# UD3_1_N_P_Gate_Driver.net
KiCad netlist of a schematic drawn in Altium Designer
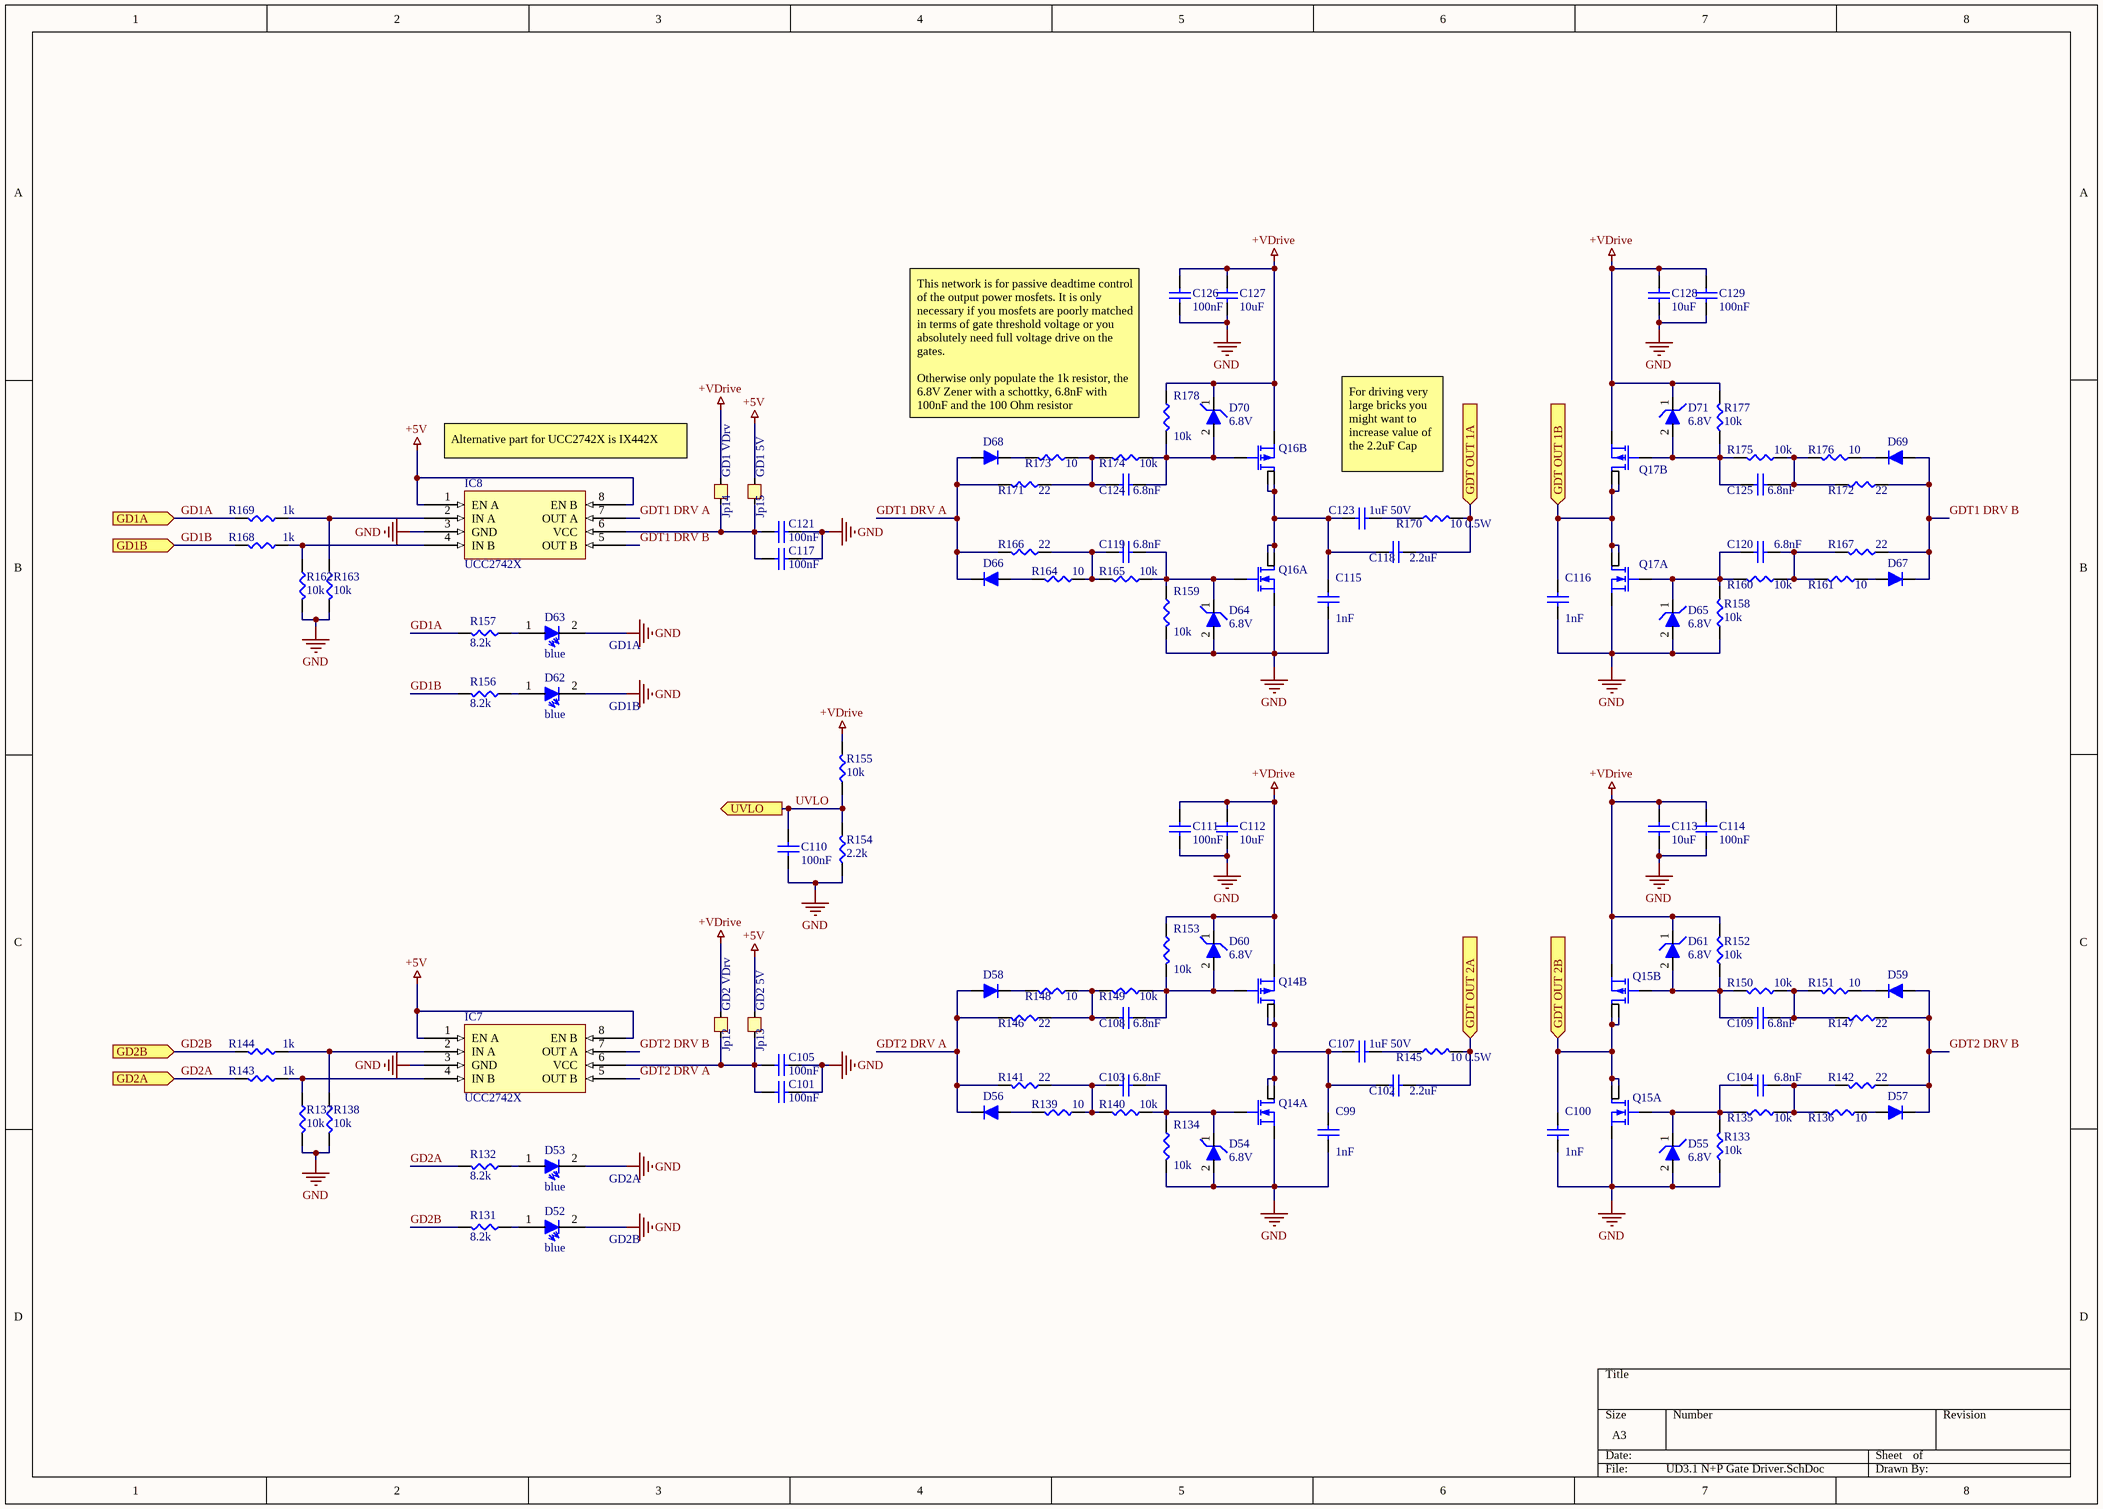
[diagram p0: UD3.1 N+P Gate Driver.SchDoc]

(export (version "E")
  (design (tool "Eeschema 10.0.6"))
  (components
    (comp (ref "C99") (value "1nF") (footprint "0603") (libsource (lib "stdLib") (part "Cap")))
    (comp (ref "C100") (value "1nF") (footprint "0603") (libsource (lib "stdLib") (part "Cap")))
    (comp (ref "C101") (value "100nF") (footprint "0603") (libsource (lib "stdLib") (part "Cap")))
    (comp (ref "C102") (value "2.2uF") (footprint "1210") (libsource (lib "stdLib") (part "Cap")))
    (comp (ref "C103") (value "6.8nF") (footprint "0603") (libsource (lib "stdLib") (part "Cap")))
    (comp (ref "C104") (value "6.8nF") (footprint "0603") (libsource (lib "stdLib") (part "Cap")))
    (comp (ref "C105") (value "100nF") (footprint "0603") (libsource (lib "stdLib") (part "Cap")))
    (comp (ref "C107") (value "1uF 50V") (footprint "1210") (libsource (lib "stdLib") (part "Cap")))
    (comp (ref "C108") (value "6.8nF") (footprint "0603") (libsource (lib "stdLib") (part "Cap")))
    (comp (ref "C109") (value "6.8nF") (footprint "0603") (libsource (lib "stdLib") (part "Cap")))
    (comp (ref "C110") (value "100nF") (footprint "0603") (libsource (lib "stdLib") (part "Cap")))
    (comp (ref "C111") (value "100nF") (footprint "0603") (libsource (lib "stdLib") (part "Cap")))
    (comp (ref "C112") (value "10uF") (footprint "0805") (libsource (lib "stdLib") (part "Cap")))
    (comp (ref "C113") (value "10uF") (footprint "0805") (libsource (lib "stdLib") (part "Cap")))
    (comp (ref "C114") (value "100nF") (footprint "0603") (libsource (lib "stdLib") (part "Cap")))
    (comp (ref "C115") (value "1nF") (footprint "0603") (libsource (lib "stdLib") (part "Cap")))
    (comp (ref "C116") (value "1nF") (footprint "0603") (libsource (lib "stdLib") (part "Cap")))
    (comp (ref "C117") (value "100nF") (footprint "0603") (libsource (lib "stdLib") (part "Cap")))
    (comp (ref "C118") (value "2.2uF") (footprint "1210") (libsource (lib "stdLib") (part "Cap")))
    (comp (ref "C119") (value "6.8nF") (footprint "0603") (libsource (lib "stdLib") (part "Cap")))
    (comp (ref "C120") (value "6.8nF") (footprint "0603") (libsource (lib "stdLib") (part "Cap")))
    (comp (ref "C121") (value "100nF") (footprint "0603") (libsource (lib "stdLib") (part "Cap")))
    (comp (ref "C123") (value "1uF 50V") (footprint "1210") (libsource (lib "stdLib") (part "Cap")))
    (comp (ref "C124") (value "6.8nF") (footprint "0603") (libsource (lib "stdLib") (part "Cap")))
    (comp (ref "C125") (value "6.8nF") (footprint "0603") (libsource (lib "stdLib") (part "Cap")))
    (comp (ref "C126") (value "100nF") (footprint "0603") (libsource (lib "stdLib") (part "Cap")))
    (comp (ref "C127") (value "10uF") (footprint "0805") (libsource (lib "stdLib") (part "Cap")))
    (comp (ref "C128") (value "10uF") (footprint "0805") (libsource (lib "stdLib") (part "Cap")))
    (comp (ref "C129") (value "100nF") (footprint "0603") (libsource (lib "stdLib") (part "Cap")))
    (comp (ref "D52")
      (value "blue")
      (footprint "1206 Reverse Mount")
      (description "Diode, but it lights up")
      (libsource (lib "stdLib") (part "LED"))
    )
    (comp (ref "D53")
      (value "blue")
      (footprint "1206 Reverse Mount")
      (description "Diode, but it lights up")
      (libsource (lib "stdLib") (part "LED"))
    )
    (comp (ref "D54") (value "6.8V") (footprint "SOD523") (libsource (lib "stdLib") (part "Diode Zener")))
    (comp (ref "D55") (value "6.8V") (footprint "SOD523") (libsource (lib "stdLib") (part "Diode Zener")))
    (comp (ref "D56")
      (value "Schottky 30V 100mA")
      (footprint "SOD523")
      (description "Cmon its a diode what more do I need to say?")
      (libsource (lib "stdLib") (part "Diode"))
    )
    (comp (ref "D57")
      (value "Schottky 30V 100mA")
      (footprint "SOD523")
      (description "Cmon its a diode what more do I need to say?")
      (libsource (lib "stdLib") (part "Diode"))
    )
    (comp (ref "D58")
      (value "Schottky 30V 100mA")
      (footprint "SOD523")
      (description "Cmon its a diode what more do I need to say?")
      (libsource (lib "stdLib") (part "Diode"))
    )
    (comp (ref "D59")
      (value "Schottky 30V 100mA")
      (footprint "SOD523")
      (description "Cmon its a diode what more do I need to say?")
      (libsource (lib "stdLib") (part "Diode"))
    )
    (comp (ref "D60") (value "6.8V") (footprint "SOD523") (libsource (lib "stdLib") (part "Diode Zener")))
    (comp (ref "D61") (value "6.8V") (footprint "SOD523") (libsource (lib "stdLib") (part "Diode Zener")))
    (comp (ref "D62")
      (value "blue")
      (footprint "1206 Reverse Mount")
      (description "Diode, but it lights up")
      (libsource (lib "stdLib") (part "LED"))
    )
    (comp (ref "D63")
      (value "blue")
      (footprint "1206 Reverse Mount")
      (description "Diode, but it lights up")
      (libsource (lib "stdLib") (part "LED"))
    )
    (comp (ref "D64") (value "6.8V") (footprint "SOD523") (libsource (lib "stdLib") (part "Diode Zener")))
    (comp (ref "D65") (value "6.8V") (footprint "SOD523") (libsource (lib "stdLib") (part "Diode Zener")))
    (comp (ref "D66")
      (value "Schottky 30V 100mA")
      (footprint "SOD523")
      (description "Cmon its a diode what more do I need to say?")
      (libsource (lib "stdLib") (part "Diode"))
    )
    (comp (ref "D67")
      (value "Schottky 30V 100mA")
      (footprint "SOD523")
      (description "Cmon its a diode what more do I need to say?")
      (libsource (lib "stdLib") (part "Diode"))
    )
    (comp (ref "D68")
      (value "Schottky 30V 100mA")
      (footprint "SOD523")
      (description "Cmon its a diode what more do I need to say?")
      (libsource (lib "stdLib") (part "Diode"))
    )
    (comp (ref "D69")
      (value "Schottky 30V 100mA")
      (footprint "SOD523")
      (description "Cmon its a diode what more do I need to say?")
      (libsource (lib "stdLib") (part "Diode"))
    )
    (comp (ref "D70") (value "6.8V") (footprint "SOD523") (libsource (lib "stdLib") (part "Diode Zener")))
    (comp (ref "D71") (value "6.8V") (footprint "SOD523") (libsource (lib "stdLib") (part "Diode Zener")))
    (comp (ref "IC7")
      (value "UCC2742X")
      (footprint "SOIC8")
      (description "Dual gate driver")
      (libsource (lib "stdLib") (part "UCC2742X"))
    )
    (comp (ref "IC8")
      (value "UCC2742X")
      (footprint "SOIC8")
      (description "Dual gate driver")
      (libsource (lib "stdLib") (part "UCC2742X"))
    )
    (comp (ref "Jp12")
      (value "GD2 VDrv")
      (footprint "PCB Jumper NO")
      (libsource (lib "stdLib") (part "Jumper"))
    )
    (comp (ref "Jp13")
      (value "GD2 5V")
      (footprint "PCB Jumper NO")
      (libsource (lib "stdLib") (part "Jumper"))
    )
    (comp (ref "Jp14")
      (value "GD1 VDrv")
      (footprint "PCB Jumper NO")
      (libsource (lib "stdLib") (part "Jumper"))
    )
    (comp (ref "Jp15")
      (value "GD1 5V")
      (footprint "PCB Jumper NO")
      (libsource (lib "stdLib") (part "Jumper"))
    )
    (comp (ref "Q14")
      (value "Mosfet 1N1P")
      (footprint "SO-8FL - Dual")
      (description "Dual Mosfet, one N & P channel resp.")
      (libsource (lib "stdLib") (part "Mosfet 1N1P"))
    )
    (comp (ref "Q15")
      (value "Mosfet 1N1P")
      (footprint "SO-8FL - Dual")
      (description "Dual Mosfet, one N & P channel resp.")
      (libsource (lib "stdLib") (part "Mosfet 1N1P"))
    )
    (comp (ref "Q16")
      (value "Mosfet 1N1P")
      (footprint "SO-8FL - Dual")
      (description "Dual Mosfet, one N & P channel resp.")
      (libsource (lib "stdLib") (part "Mosfet 1N1P"))
    )
    (comp (ref "Q17")
      (value "Mosfet 1N1P")
      (footprint "SO-8FL - Dual")
      (description "Dual Mosfet, one N & P channel resp.")
      (libsource (lib "stdLib") (part "Mosfet 1N1P"))
    )
    (comp (ref "R131") (value "8.2k") (footprint "0603") (libsource (lib "stdLib") (part "Resistor")))
    (comp (ref "R132") (value "8.2k") (footprint "0603") (libsource (lib "stdLib") (part "Resistor")))
    (comp (ref "R133") (value "10k") (footprint "0603") (libsource (lib "stdLib") (part "Resistor")))
    (comp (ref "R134") (value "10k") (footprint "0603") (libsource (lib "stdLib") (part "Resistor")))
    (comp (ref "R135") (value "10k") (footprint "0603") (libsource (lib "stdLib") (part "Resistor")))
    (comp (ref "R136") (value "10") (footprint "0603") (libsource (lib "stdLib") (part "Resistor")))
    (comp (ref "R137") (value "10k") (footprint "0603") (libsource (lib "stdLib") (part "Resistor")))
    (comp (ref "R138") (value "10k") (footprint "0603") (libsource (lib "stdLib") (part "Resistor")))
    (comp (ref "R139") (value "10") (footprint "0603") (libsource (lib "stdLib") (part "Resistor")))
    (comp (ref "R140") (value "10k") (footprint "0603") (libsource (lib "stdLib") (part "Resistor")))
    (comp (ref "R141") (value "22") (footprint "0603") (libsource (lib "stdLib") (part "Resistor")))
    (comp (ref "R142") (value "22") (footprint "0603") (libsource (lib "stdLib") (part "Resistor")))
    (comp (ref "R143") (value "1k") (footprint "0603") (libsource (lib "stdLib") (part "Resistor")))
    (comp (ref "R144") (value "1k") (footprint "0603") (libsource (lib "stdLib") (part "Resistor")))
    (comp (ref "R145") (value "10 0.5W") (footprint "1210") (libsource (lib "stdLib") (part "Resistor")))
    (comp (ref "R146") (value "22") (footprint "0603") (libsource (lib "stdLib") (part "Resistor")))
    (comp (ref "R147") (value "22") (footprint "0603") (libsource (lib "stdLib") (part "Resistor")))
    (comp (ref "R148") (value "10") (footprint "0603") (libsource (lib "stdLib") (part "Resistor")))
    (comp (ref "R149") (value "10k") (footprint "0603") (libsource (lib "stdLib") (part "Resistor")))
    (comp (ref "R150") (value "10k") (footprint "0603") (libsource (lib "stdLib") (part "Resistor")))
    (comp (ref "R151") (value "10") (footprint "0603") (libsource (lib "stdLib") (part "Resistor")))
    (comp (ref "R152") (value "10k") (footprint "0603") (libsource (lib "stdLib") (part "Resistor")))
    (comp (ref "R153") (value "10k") (footprint "0603") (libsource (lib "stdLib") (part "Resistor")))
    (comp (ref "R154") (value "2.2k") (footprint "0603") (libsource (lib "stdLib") (part "Resistor")))
    (comp (ref "R155") (value "10k") (footprint "0603") (libsource (lib "stdLib") (part "Resistor")))
    (comp (ref "R156") (value "8.2k") (footprint "0603") (libsource (lib "stdLib") (part "Resistor")))
    (comp (ref "R157") (value "8.2k") (footprint "0603") (libsource (lib "stdLib") (part "Resistor")))
    (comp (ref "R158") (value "10k") (footprint "0603") (libsource (lib "stdLib") (part "Resistor")))
    (comp (ref "R159") (value "10k") (footprint "0603") (libsource (lib "stdLib") (part "Resistor")))
    (comp (ref "R160") (value "10k") (footprint "0603") (libsource (lib "stdLib") (part "Resistor")))
    (comp (ref "R161") (value "10") (footprint "0603") (libsource (lib "stdLib") (part "Resistor")))
    (comp (ref "R162") (value "10k") (footprint "0603") (libsource (lib "stdLib") (part "Resistor")))
    (comp (ref "R163") (value "10k") (footprint "0603") (libsource (lib "stdLib") (part "Resistor")))
    (comp (ref "R164") (value "10") (footprint "0603") (libsource (lib "stdLib") (part "Resistor")))
    (comp (ref "R165") (value "10k") (footprint "0603") (libsource (lib "stdLib") (part "Resistor")))
    (comp (ref "R166") (value "22") (footprint "0603") (libsource (lib "stdLib") (part "Resistor")))
    (comp (ref "R167") (value "22") (footprint "0603") (libsource (lib "stdLib") (part "Resistor")))
    (comp (ref "R168") (value "1k") (footprint "0603") (libsource (lib "stdLib") (part "Resistor")))
    (comp (ref "R169") (value "1k") (footprint "0603") (libsource (lib "stdLib") (part "Resistor")))
    (comp (ref "R170") (value "10 0.5W") (footprint "1210") (libsource (lib "stdLib") (part "Resistor")))
    (comp (ref "R171") (value "22") (footprint "0603") (libsource (lib "stdLib") (part "Resistor")))
    (comp (ref "R172") (value "22") (footprint "0603") (libsource (lib "stdLib") (part "Resistor")))
    (comp (ref "R173") (value "10") (footprint "0603") (libsource (lib "stdLib") (part "Resistor")))
    (comp (ref "R174") (value "10k") (footprint "0603") (libsource (lib "stdLib") (part "Resistor")))
    (comp (ref "R175") (value "10k") (footprint "0603") (libsource (lib "stdLib") (part "Resistor")))
    (comp (ref "R176") (value "10") (footprint "0603") (libsource (lib "stdLib") (part "Resistor")))
    (comp (ref "R177") (value "10k") (footprint "0603") (libsource (lib "stdLib") (part "Resistor")))
    (comp (ref "R178") (value "10k") (footprint "0603") (libsource (lib "stdLib") (part "Resistor")))
  )
  (nets
    (net (code "1") (name "+5V") (class "Default")
      (node (ref "IC7") (pin "1") (pinfunction "EN_A_1") (pintype "input"))
      (node (ref "IC7") (pin "8") (pinfunction "EN_B_8") (pintype "input"))
      (node (ref "IC8") (pin "1") (pinfunction "EN_A_1") (pintype "input"))
      (node (ref "IC8") (pin "8") (pinfunction "EN_B_8") (pintype "input"))
      (node (ref "Jp13") (pin "2") (pinfunction "2_2") (pintype "passive"))
      (node (ref "Jp15") (pin "2") (pinfunction "2_2") (pintype "passive"))
    )
    (net (code "2") (name "+VDrive") (class "Default")
      (node (ref "C111") (pin "2") (pinfunction "2_2") (pintype "passive"))
      (node (ref "C112") (pin "2") (pinfunction "2_2") (pintype "passive"))
      (node (ref "C113") (pin "2") (pinfunction "2_2") (pintype "passive"))
      (node (ref "C114") (pin "2") (pinfunction "2_2") (pintype "passive"))
      (node (ref "C126") (pin "2") (pinfunction "2_2") (pintype "passive"))
      (node (ref "C127") (pin "2") (pinfunction "2_2") (pintype "passive"))
      (node (ref "C128") (pin "2") (pinfunction "2_2") (pintype "passive"))
      (node (ref "C129") (pin "2") (pinfunction "2_2") (pintype "passive"))
      (node (ref "D60") (pin "1") (pintype "passive"))
      (node (ref "D61") (pin "1") (pintype "passive"))
      (node (ref "D70") (pin "1") (pintype "passive"))
      (node (ref "D71") (pin "1") (pintype "passive"))
      (node (ref "Jp12") (pin "2") (pinfunction "2_2") (pintype "passive"))
      (node (ref "Jp14") (pin "2") (pinfunction "2_2") (pintype "passive"))
      (node (ref "Q14") (pin "Sp") (pinfunction "Sp_Sp") (pintype "passive"))
      (node (ref "Q15") (pin "Sp") (pinfunction "Sp_Sp") (pintype "passive"))
      (node (ref "Q16") (pin "Sp") (pinfunction "Sp_Sp") (pintype "passive"))
      (node (ref "Q17") (pin "Sp") (pinfunction "Sp_Sp") (pintype "passive"))
      (node (ref "R152") (pin "2") (pinfunction "2_2") (pintype "passive"))
      (node (ref "R153") (pin "2") (pinfunction "2_2") (pintype "passive"))
      (node (ref "R155") (pin "1") (pinfunction "1_1") (pintype "passive"))
      (node (ref "R177") (pin "2") (pinfunction "2_2") (pintype "passive"))
      (node (ref "R178") (pin "2") (pinfunction "2_2") (pintype "passive"))
    )
    (net (code "3") (name "/GD1A") (class "Default")
      (node (ref "R157") (pin "1") (pinfunction "1_1") (pintype "passive"))
      (node (ref "R169") (pin "1") (pinfunction "1_1") (pintype "passive"))
    )
    (net (code "4") (name "/GD1B") (class "Default")
      (node (ref "R156") (pin "1") (pinfunction "1_1") (pintype "passive"))
      (node (ref "R168") (pin "1") (pinfunction "1_1") (pintype "passive"))
    )
    (net (code "5") (name "/GD2A") (class "Default")
      (node (ref "R132") (pin "1") (pinfunction "1_1") (pintype "passive"))
      (node (ref "R143") (pin "1") (pinfunction "1_1") (pintype "passive"))
    )
    (net (code "6") (name "/GD2B") (class "Default")
      (node (ref "R131") (pin "1") (pinfunction "1_1") (pintype "passive"))
      (node (ref "R144") (pin "1") (pinfunction "1_1") (pintype "passive"))
    )
    (net (code "7") (name "/GDT OUT 1A") (class "Default")
      (node (ref "C118") (pin "2") (pinfunction "2_2") (pintype "passive"))
      (node (ref "R170") (pin "2") (pinfunction "2_2") (pintype "passive"))
    )
    (net (code "8") (name "/GDT OUT 1B") (class "Default")
      (node (ref "C116") (pin "2") (pinfunction "2_2") (pintype "passive"))
      (node (ref "Q17") (pin "Dn1") (pinfunction "Dn1_Dn1") (pintype "passive"))
      (node (ref "Q17") (pin "Dn2") (pinfunction "Dn2_Dn2") (pintype "passive"))
      (node (ref "Q17") (pin "Dp1") (pinfunction "Dp1_Dp1") (pintype "passive"))
      (node (ref "Q17") (pin "Dp2") (pinfunction "Dp2_Dp2") (pintype "passive"))
    )
    (net (code "9") (name "/GDT OUT 2A") (class "Default")
      (node (ref "C102") (pin "2") (pinfunction "2_2") (pintype "passive"))
      (node (ref "R145") (pin "2") (pinfunction "2_2") (pintype "passive"))
    )
    (net (code "10") (name "/GDT OUT 2B") (class "Default")
      (node (ref "C100") (pin "2") (pinfunction "2_2") (pintype "passive"))
      (node (ref "Q15") (pin "Dn1") (pinfunction "Dn1_Dn1") (pintype "passive"))
      (node (ref "Q15") (pin "Dn2") (pinfunction "Dn2_Dn2") (pintype "passive"))
      (node (ref "Q15") (pin "Dp1") (pinfunction "Dp1_Dp1") (pintype "passive"))
      (node (ref "Q15") (pin "Dp2") (pinfunction "Dp2_Dp2") (pintype "passive"))
    )
    (net (code "11") (name "/GDT1 DRV A") (class "Default")
      (node (ref "D66") (pin "2") (pintype "passive"))
      (node (ref "D68") (pin "1") (pintype "passive"))
      (node (ref "IC8") (pin "7") (pinfunction "OUT_A_7") (pintype "input"))
      (node (ref "R166") (pin "1") (pinfunction "1_1") (pintype "passive"))
      (node (ref "R171") (pin "1") (pinfunction "1_1") (pintype "passive"))
    )
    (net (code "12") (name "/GDT1 DRV B") (class "Default")
      (node (ref "D67") (pin "2") (pintype "passive"))
      (node (ref "D69") (pin "1") (pintype "passive"))
      (node (ref "IC8") (pin "5") (pinfunction "OUT_B_5") (pintype "input"))
      (node (ref "R167") (pin "1") (pinfunction "1_1") (pintype "passive"))
      (node (ref "R172") (pin "1") (pinfunction "1_1") (pintype "passive"))
    )
    (net (code "13") (name "/GDT2 DRV A") (class "Default")
      (node (ref "D56") (pin "2") (pintype "passive"))
      (node (ref "D58") (pin "1") (pintype "passive"))
      (node (ref "IC7") (pin "5") (pinfunction "OUT_B_5") (pintype "input"))
      (node (ref "R141") (pin "1") (pinfunction "1_1") (pintype "passive"))
      (node (ref "R146") (pin "1") (pinfunction "1_1") (pintype "passive"))
    )
    (net (code "14") (name "/GDT2 DRV B") (class "Default")
      (node (ref "D57") (pin "2") (pintype "passive"))
      (node (ref "D59") (pin "1") (pintype "passive"))
      (node (ref "IC7") (pin "7") (pinfunction "OUT_A_7") (pintype "input"))
      (node (ref "R142") (pin "1") (pinfunction "1_1") (pintype "passive"))
      (node (ref "R147") (pin "1") (pinfunction "1_1") (pintype "passive"))
    )
    (net (code "15") (name "/UVLO") (class "Default")
      (node (ref "C110") (pin "2") (pinfunction "2_2") (pintype "passive"))
      (node (ref "R154") (pin "1") (pinfunction "1_1") (pintype "passive"))
      (node (ref "R155") (pin "2") (pinfunction "2_2") (pintype "passive"))
    )
    (net (code "16") (name "GND") (class "Default")
      (node (ref "C100") (pin "1") (pinfunction "1_1") (pintype "passive"))
      (node (ref "C101") (pin "2") (pinfunction "2_2") (pintype "passive"))
      (node (ref "C105") (pin "2") (pinfunction "2_2") (pintype "passive"))
      (node (ref "C110") (pin "1") (pinfunction "1_1") (pintype "passive"))
      (node (ref "C111") (pin "1") (pinfunction "1_1") (pintype "passive"))
      (node (ref "C112") (pin "1") (pinfunction "1_1") (pintype "passive"))
      (node (ref "C113") (pin "1") (pinfunction "1_1") (pintype "passive"))
      (node (ref "C114") (pin "1") (pinfunction "1_1") (pintype "passive"))
      (node (ref "C115") (pin "1") (pinfunction "1_1") (pintype "passive"))
      (node (ref "C116") (pin "1") (pinfunction "1_1") (pintype "passive"))
      (node (ref "C117") (pin "2") (pinfunction "2_2") (pintype "passive"))
      (node (ref "C121") (pin "2") (pinfunction "2_2") (pintype "passive"))
      (node (ref "C126") (pin "1") (pinfunction "1_1") (pintype "passive"))
      (node (ref "C127") (pin "1") (pinfunction "1_1") (pintype "passive"))
      (node (ref "C128") (pin "1") (pinfunction "1_1") (pintype "passive"))
      (node (ref "C129") (pin "1") (pinfunction "1_1") (pintype "passive"))
      (node (ref "C99") (pin "1") (pinfunction "1_1") (pintype "passive"))
      (node (ref "D52") (pin "2") (pintype "passive"))
      (node (ref "D53") (pin "2") (pintype "passive"))
      (node (ref "D54") (pin "2") (pintype "passive"))
      (node (ref "D55") (pin "2") (pintype "passive"))
      (node (ref "D62") (pin "2") (pintype "passive"))
      (node (ref "D63") (pin "2") (pintype "passive"))
      (node (ref "D64") (pin "2") (pintype "passive"))
      (node (ref "D65") (pin "2") (pintype "passive"))
      (node (ref "IC7") (pin "3") (pinfunction "GND_3") (pintype "input"))
      (node (ref "IC8") (pin "3") (pinfunction "GND_3") (pintype "input"))
      (node (ref "Q14") (pin "Sn") (pinfunction "Sn_Sn") (pintype "passive"))
      (node (ref "Q15") (pin "Sn") (pinfunction "Sn_Sn") (pintype "passive"))
      (node (ref "Q16") (pin "Sn") (pinfunction "Sn_Sn") (pintype "passive"))
      (node (ref "Q17") (pin "Sn") (pinfunction "Sn_Sn") (pintype "passive"))
      (node (ref "R133") (pin "1") (pinfunction "1_1") (pintype "passive"))
      (node (ref "R134") (pin "1") (pinfunction "1_1") (pintype "passive"))
      (node (ref "R137") (pin "1") (pinfunction "1_1") (pintype "passive"))
      (node (ref "R138") (pin "1") (pinfunction "1_1") (pintype "passive"))
      (node (ref "R154") (pin "2") (pinfunction "2_2") (pintype "passive"))
      (node (ref "R158") (pin "1") (pinfunction "1_1") (pintype "passive"))
      (node (ref "R159") (pin "1") (pinfunction "1_1") (pintype "passive"))
      (node (ref "R162") (pin "1") (pinfunction "1_1") (pintype "passive"))
      (node (ref "R163") (pin "1") (pinfunction "1_1") (pintype "passive"))
    )
    (net (code "17") (name "Net-(C102-Pad1)") (class "Default")
      (node (ref "C102") (pin "1") (pinfunction "1_1") (pintype "passive"))
      (node (ref "C107") (pin "1") (pinfunction "1_1") (pintype "passive"))
      (node (ref "C99") (pin "2") (pinfunction "2_2") (pintype "passive"))
      (node (ref "Q14") (pin "Dn1") (pinfunction "Dn1_Dn1") (pintype "passive"))
      (node (ref "Q14") (pin "Dn2") (pinfunction "Dn2_Dn2") (pintype "passive"))
      (node (ref "Q14") (pin "Dp1") (pinfunction "Dp1_Dp1") (pintype "passive"))
      (node (ref "Q14") (pin "Dp2") (pinfunction "Dp2_Dp2") (pintype "passive"))
    )
    (net (code "18") (name "Net-(C103-Pad1)") (class "Default")
      (node (ref "C103") (pin "1") (pinfunction "1_1") (pintype "passive"))
      (node (ref "R139") (pin "2") (pinfunction "2_2") (pintype "passive"))
      (node (ref "R140") (pin "1") (pinfunction "1_1") (pintype "passive"))
      (node (ref "R141") (pin "2") (pinfunction "2_2") (pintype "passive"))
    )
    (net (code "19") (name "Net-(C103-Pad2)") (class "Default")
      (node (ref "C103") (pin "2") (pinfunction "2_2") (pintype "passive"))
      (node (ref "D54") (pin "1") (pintype "passive"))
      (node (ref "Q14") (pin "Gn") (pinfunction "Gn_Gn") (pintype "passive"))
      (node (ref "R134") (pin "2") (pinfunction "2_2") (pintype "passive"))
      (node (ref "R140") (pin "2") (pinfunction "2_2") (pintype "passive"))
    )
    (net (code "20") (name "Net-(C104-Pad1)") (class "Default")
      (node (ref "C104") (pin "1") (pinfunction "1_1") (pintype "passive"))
      (node (ref "R135") (pin "1") (pinfunction "1_1") (pintype "passive"))
      (node (ref "R136") (pin "2") (pinfunction "2_2") (pintype "passive"))
      (node (ref "R142") (pin "2") (pinfunction "2_2") (pintype "passive"))
    )
    (net (code "21") (name "Net-(C104-Pad2)") (class "Default")
      (node (ref "C104") (pin "2") (pinfunction "2_2") (pintype "passive"))
      (node (ref "D55") (pin "1") (pintype "passive"))
      (node (ref "Q15") (pin "Gn") (pinfunction "Gn_Gn") (pintype "passive"))
      (node (ref "R133") (pin "2") (pinfunction "2_2") (pintype "passive"))
      (node (ref "R135") (pin "2") (pinfunction "2_2") (pintype "passive"))
    )
    (net (code "22") (name "Net-(C107-Pad2)") (class "Default")
      (node (ref "C107") (pin "2") (pinfunction "2_2") (pintype "passive"))
      (node (ref "R145") (pin "1") (pinfunction "1_1") (pintype "passive"))
    )
    (net (code "23") (name "Net-(C108-Pad1)") (class "Default")
      (node (ref "C108") (pin "1") (pinfunction "1_1") (pintype "passive"))
      (node (ref "R146") (pin "2") (pinfunction "2_2") (pintype "passive"))
      (node (ref "R148") (pin "2") (pinfunction "2_2") (pintype "passive"))
      (node (ref "R149") (pin "1") (pinfunction "1_1") (pintype "passive"))
    )
    (net (code "24") (name "Net-(C108-Pad2)") (class "Default")
      (node (ref "C108") (pin "2") (pinfunction "2_2") (pintype "passive"))
      (node (ref "D60") (pin "2") (pintype "passive"))
      (node (ref "Q14") (pin "Gp") (pinfunction "Gp_Gp") (pintype "passive"))
      (node (ref "R149") (pin "2") (pinfunction "2_2") (pintype "passive"))
      (node (ref "R153") (pin "1") (pinfunction "1_1") (pintype "passive"))
    )
    (net (code "25") (name "Net-(C109-Pad1)") (class "Default")
      (node (ref "C109") (pin "1") (pinfunction "1_1") (pintype "passive"))
      (node (ref "R147") (pin "2") (pinfunction "2_2") (pintype "passive"))
      (node (ref "R150") (pin "1") (pinfunction "1_1") (pintype "passive"))
      (node (ref "R151") (pin "2") (pinfunction "2_2") (pintype "passive"))
    )
    (net (code "26") (name "Net-(C109-Pad2)") (class "Default")
      (node (ref "C109") (pin "2") (pinfunction "2_2") (pintype "passive"))
      (node (ref "D61") (pin "2") (pintype "passive"))
      (node (ref "Q15") (pin "Gp") (pinfunction "Gp_Gp") (pintype "passive"))
      (node (ref "R150") (pin "2") (pinfunction "2_2") (pintype "passive"))
      (node (ref "R152") (pin "1") (pinfunction "1_1") (pintype "passive"))
    )
    (net (code "27") (name "Net-(C115-Pad2)") (class "Default")
      (node (ref "C115") (pin "2") (pinfunction "2_2") (pintype "passive"))
      (node (ref "C118") (pin "1") (pinfunction "1_1") (pintype "passive"))
      (node (ref "C123") (pin "1") (pinfunction "1_1") (pintype "passive"))
      (node (ref "Q16") (pin "Dn1") (pinfunction "Dn1_Dn1") (pintype "passive"))
      (node (ref "Q16") (pin "Dn2") (pinfunction "Dn2_Dn2") (pintype "passive"))
      (node (ref "Q16") (pin "Dp1") (pinfunction "Dp1_Dp1") (pintype "passive"))
      (node (ref "Q16") (pin "Dp2") (pinfunction "Dp2_Dp2") (pintype "passive"))
    )
    (net (code "28") (name "Net-(C119-Pad1)") (class "Default")
      (node (ref "C119") (pin "1") (pinfunction "1_1") (pintype "passive"))
      (node (ref "R164") (pin "2") (pinfunction "2_2") (pintype "passive"))
      (node (ref "R165") (pin "1") (pinfunction "1_1") (pintype "passive"))
      (node (ref "R166") (pin "2") (pinfunction "2_2") (pintype "passive"))
    )
    (net (code "29") (name "Net-(C119-Pad2)") (class "Default")
      (node (ref "C119") (pin "2") (pinfunction "2_2") (pintype "passive"))
      (node (ref "D64") (pin "1") (pintype "passive"))
      (node (ref "Q16") (pin "Gn") (pinfunction "Gn_Gn") (pintype "passive"))
      (node (ref "R159") (pin "2") (pinfunction "2_2") (pintype "passive"))
      (node (ref "R165") (pin "2") (pinfunction "2_2") (pintype "passive"))
    )
    (net (code "30") (name "Net-(C120-Pad1)") (class "Default")
      (node (ref "C120") (pin "1") (pinfunction "1_1") (pintype "passive"))
      (node (ref "R160") (pin "1") (pinfunction "1_1") (pintype "passive"))
      (node (ref "R161") (pin "2") (pinfunction "2_2") (pintype "passive"))
      (node (ref "R167") (pin "2") (pinfunction "2_2") (pintype "passive"))
    )
    (net (code "31") (name "Net-(C120-Pad2)") (class "Default")
      (node (ref "C120") (pin "2") (pinfunction "2_2") (pintype "passive"))
      (node (ref "D65") (pin "1") (pintype "passive"))
      (node (ref "Q17") (pin "Gn") (pinfunction "Gn_Gn") (pintype "passive"))
      (node (ref "R158") (pin "2") (pinfunction "2_2") (pintype "passive"))
      (node (ref "R160") (pin "2") (pinfunction "2_2") (pintype "passive"))
    )
    (net (code "32") (name "Net-(C123-Pad2)") (class "Default")
      (node (ref "C123") (pin "2") (pinfunction "2_2") (pintype "passive"))
      (node (ref "R170") (pin "1") (pinfunction "1_1") (pintype "passive"))
    )
    (net (code "33") (name "Net-(C124-Pad1)") (class "Default")
      (node (ref "C124") (pin "1") (pinfunction "1_1") (pintype "passive"))
      (node (ref "R171") (pin "2") (pinfunction "2_2") (pintype "passive"))
      (node (ref "R173") (pin "2") (pinfunction "2_2") (pintype "passive"))
      (node (ref "R174") (pin "1") (pinfunction "1_1") (pintype "passive"))
    )
    (net (code "34") (name "Net-(C124-Pad2)") (class "Default")
      (node (ref "C124") (pin "2") (pinfunction "2_2") (pintype "passive"))
      (node (ref "D70") (pin "2") (pintype "passive"))
      (node (ref "Q16") (pin "Gp") (pinfunction "Gp_Gp") (pintype "passive"))
      (node (ref "R174") (pin "2") (pinfunction "2_2") (pintype "passive"))
      (node (ref "R178") (pin "1") (pinfunction "1_1") (pintype "passive"))
    )
    (net (code "35") (name "Net-(C125-Pad1)") (class "Default")
      (node (ref "C125") (pin "1") (pinfunction "1_1") (pintype "passive"))
      (node (ref "R172") (pin "2") (pinfunction "2_2") (pintype "passive"))
      (node (ref "R175") (pin "1") (pinfunction "1_1") (pintype "passive"))
      (node (ref "R176") (pin "2") (pinfunction "2_2") (pintype "passive"))
    )
    (net (code "36") (name "Net-(C125-Pad2)") (class "Default")
      (node (ref "C125") (pin "2") (pinfunction "2_2") (pintype "passive"))
      (node (ref "D71") (pin "2") (pintype "passive"))
      (node (ref "Q17") (pin "Gp") (pinfunction "Gp_Gp") (pintype "passive"))
      (node (ref "R175") (pin "2") (pinfunction "2_2") (pintype "passive"))
      (node (ref "R177") (pin "1") (pinfunction "1_1") (pintype "passive"))
    )
    (net (code "37") (name "Net-(D52-Pad1)") (class "Default")
      (node (ref "D52") (pin "1") (pintype "passive"))
      (node (ref "R131") (pin "2") (pinfunction "2_2") (pintype "passive"))
    )
    (net (code "38") (name "Net-(D53-Pad1)") (class "Default")
      (node (ref "D53") (pin "1") (pintype "passive"))
      (node (ref "R132") (pin "2") (pinfunction "2_2") (pintype "passive"))
    )
    (net (code "39") (name "Net-(D56-Pad1)") (class "Default")
      (node (ref "D56") (pin "1") (pintype "passive"))
      (node (ref "R139") (pin "1") (pinfunction "1_1") (pintype "passive"))
    )
    (net (code "40") (name "Net-(D57-Pad1)") (class "Default")
      (node (ref "D57") (pin "1") (pintype "passive"))
      (node (ref "R136") (pin "1") (pinfunction "1_1") (pintype "passive"))
    )
    (net (code "41") (name "Net-(D58-Pad2)") (class "Default")
      (node (ref "D58") (pin "2") (pintype "passive"))
      (node (ref "R148") (pin "1") (pinfunction "1_1") (pintype "passive"))
    )
    (net (code "42") (name "Net-(D59-Pad2)") (class "Default")
      (node (ref "D59") (pin "2") (pintype "passive"))
      (node (ref "R151") (pin "1") (pinfunction "1_1") (pintype "passive"))
    )
    (net (code "43") (name "Net-(D62-Pad1)") (class "Default")
      (node (ref "D62") (pin "1") (pintype "passive"))
      (node (ref "R156") (pin "2") (pinfunction "2_2") (pintype "passive"))
    )
    (net (code "44") (name "Net-(D63-Pad1)") (class "Default")
      (node (ref "D63") (pin "1") (pintype "passive"))
      (node (ref "R157") (pin "2") (pinfunction "2_2") (pintype "passive"))
    )
    (net (code "45") (name "Net-(D66-Pad1)") (class "Default")
      (node (ref "D66") (pin "1") (pintype "passive"))
      (node (ref "R164") (pin "1") (pinfunction "1_1") (pintype "passive"))
    )
    (net (code "46") (name "Net-(D67-Pad1)") (class "Default")
      (node (ref "D67") (pin "1") (pintype "passive"))
      (node (ref "R161") (pin "1") (pinfunction "1_1") (pintype "passive"))
    )
    (net (code "47") (name "Net-(D68-Pad2)") (class "Default")
      (node (ref "D68") (pin "2") (pintype "passive"))
      (node (ref "R173") (pin "1") (pinfunction "1_1") (pintype "passive"))
    )
    (net (code "48") (name "Net-(D69-Pad2)") (class "Default")
      (node (ref "D69") (pin "2") (pintype "passive"))
      (node (ref "R176") (pin "1") (pinfunction "1_1") (pintype "passive"))
    )
    (net (code "49") (name "Net-(IC7-IN_A)") (class "Default")
      (node (ref "IC7") (pin "2") (pinfunction "IN_A_2") (pintype "input"))
      (node (ref "R138") (pin "2") (pinfunction "2_2") (pintype "passive"))
      (node (ref "R144") (pin "2") (pinfunction "2_2") (pintype "passive"))
    )
    (net (code "50") (name "Net-(IC7-IN_B)") (class "Default")
      (node (ref "IC7") (pin "4") (pinfunction "IN_B_4") (pintype "input"))
      (node (ref "R137") (pin "2") (pinfunction "2_2") (pintype "passive"))
      (node (ref "R143") (pin "2") (pinfunction "2_2") (pintype "passive"))
    )
    (net (code "51") (name "Net-(IC7-VCC)") (class "Default")
      (node (ref "C101") (pin "1") (pinfunction "1_1") (pintype "passive"))
      (node (ref "C105") (pin "1") (pinfunction "1_1") (pintype "passive"))
      (node (ref "IC7") (pin "6") (pinfunction "VCC_6") (pintype "input"))
      (node (ref "Jp12") (pin "1") (pinfunction "1_1") (pintype "passive"))
      (node (ref "Jp13") (pin "1") (pinfunction "1_1") (pintype "passive"))
    )
    (net (code "52") (name "Net-(IC8-IN_A)") (class "Default")
      (node (ref "IC8") (pin "2") (pinfunction "IN_A_2") (pintype "input"))
      (node (ref "R163") (pin "2") (pinfunction "2_2") (pintype "passive"))
      (node (ref "R169") (pin "2") (pinfunction "2_2") (pintype "passive"))
    )
    (net (code "53") (name "Net-(IC8-IN_B)") (class "Default")
      (node (ref "IC8") (pin "4") (pinfunction "IN_B_4") (pintype "input"))
      (node (ref "R162") (pin "2") (pinfunction "2_2") (pintype "passive"))
      (node (ref "R168") (pin "2") (pinfunction "2_2") (pintype "passive"))
    )
    (net (code "54") (name "Net-(IC8-VCC)") (class "Default")
      (node (ref "C117") (pin "1") (pinfunction "1_1") (pintype "passive"))
      (node (ref "C121") (pin "1") (pinfunction "1_1") (pintype "passive"))
      (node (ref "IC8") (pin "6") (pinfunction "VCC_6") (pintype "input"))
      (node (ref "Jp14") (pin "1") (pinfunction "1_1") (pintype "passive"))
      (node (ref "Jp15") (pin "1") (pinfunction "1_1") (pintype "passive"))
    )
  )
)
